# Sheet1.net
KiCad netlist of a schematic drawn in Altium Designer
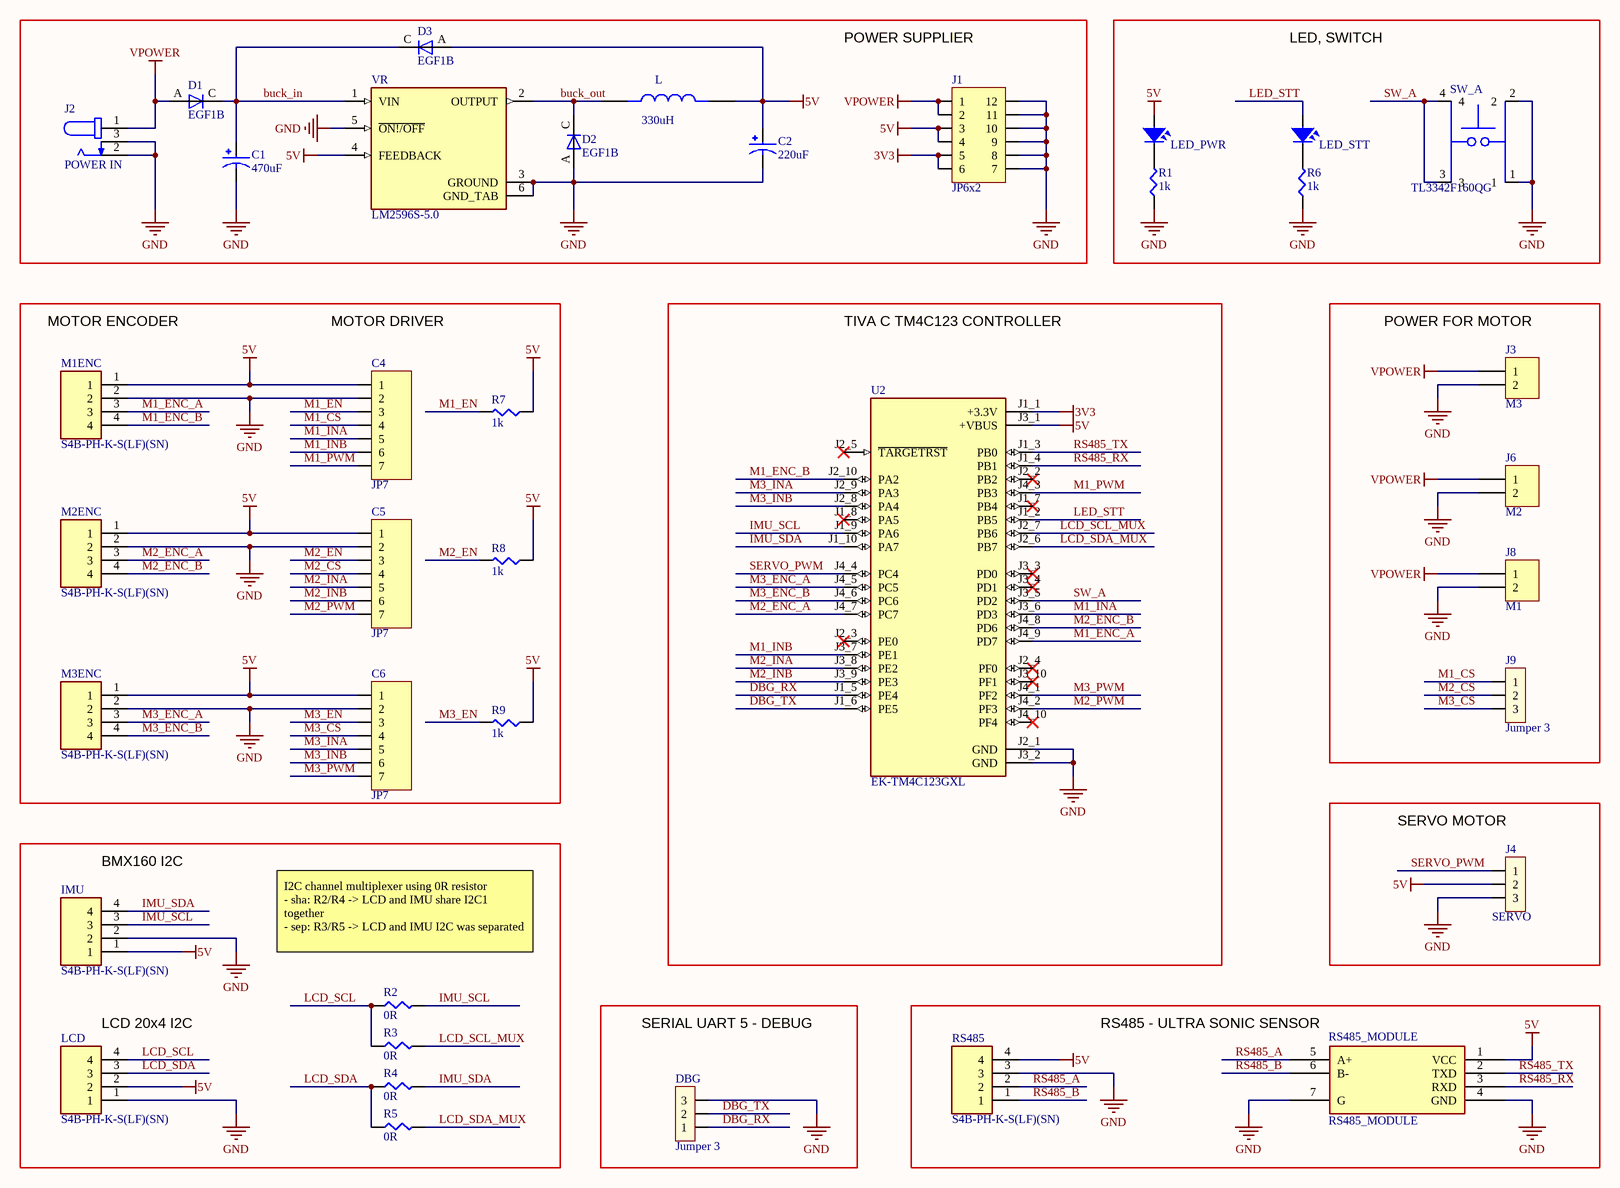
[diagram p0: Sheet1.SchDoc]

(export (version "E")
  (design (tool "Eeschema 10.0.6"))
  (components
    (comp (ref "C1")
      (value "470uF")
      (footprint "CAP_EEE2AA220P")
      (description "Capacitor; Alum Electrolytic; Cap 22 uF; Tol 20%; Vol-Rtg 100 VDC; SMT; 10x10.5; TR")
      (fields (field (name "MF") "Panasonic") (field (name "MP") "EEE-2AA220P"))
      (libsource (lib "EEE2AA220P") (part "EEE2AA220P"))
    )
    (comp (ref "C2")
      (value "220uF")
      (footprint "CAP_EEEHB1V220P")
      (description "EEE-HB Series 35 V 22 uF Ã˜ 6.3 x 5.8 mm 105 Â°C SMT V-Chip Aluminum Electrolytic")
      (fields (field (name "MP") "EEEHB1V220P") (field (name "MF") "Panasonic"))
      (libsource (lib "EEEHB1V220P") (part "EEEHB1V220P"))
    )
    (comp (ref "C4")
      (value "JP7")
      (footprint "JP7-C1T")
      (description "WR-PHD 2.54 mm Angled Socket Header")
      (fields
        (field (name "MANUFACTURER") "Würth Elektronik eiSos GmbH")
        (field (name "PARTNO") "613007143121")
        (field (name "CREATED BY") "Karrer Zheng")
      )
      (libsource (lib "My Library") (part "JP7_1"))
    )
    (comp (ref "C5")
      (value "JP7")
      (footprint "JP7-C1T")
      (description "WR-PHD 2.54 mm Angled Socket Header")
      (fields
        (field (name "MANUFACTURER") "Würth Elektronik eiSos GmbH")
        (field (name "PARTNO") "613007143121")
        (field (name "CREATED BY") "Karrer Zheng")
      )
      (libsource (lib "My Library") (part "JP7_1"))
    )
    (comp (ref "C6")
      (value "JP7")
      (footprint "JP7-C1T")
      (description "WR-PHD 2.54 mm Angled Socket Header")
      (fields
        (field (name "MANUFACTURER") "Würth Elektronik eiSos GmbH")
        (field (name "PARTNO") "613007143121")
        (field (name "CREATED BY") "Karrer Zheng")
      )
      (libsource (lib "My Library") (part "JP7_1"))
    )
    (comp (ref "D1")
      (value "EGF1B")
      (footprint "DIOM449X264X300L114X135N")
      (description "SS54 SMA\r\nDiode Shotky SS54 1N5824 5A 40V")
      (fields (field (name "MF") "ON Semiconductor"))
      (libsource (lib "EGF1B") (part "EGF1B"))
    )
    (comp (ref "D2")
      (value "EGF1B")
      (footprint "DIOM449X264X300L114X135N")
      (description "SS54 SMA\r\nDiode Shotky SS54 1N5824 5A 40V")
      (fields (field (name "MF") "ON Semiconductor"))
      (libsource (lib "EGF1B") (part "EGF1B"))
    )
    (comp (ref "D3")
      (value "EGF1B")
      (footprint "DIOM449X264X300L114X135N")
      (description "SS54 SMA\r\nDiode Shotky SS54 1N5824 5A 40V")
      (fields (field (name "MF") "ON Semiconductor"))
      (libsource (lib "EGF1B") (part "EGF1B"))
    )
    (comp (ref "DBG") (value "Jumper 3") (footprint "JP3") (libsource (lib "") (part "JP3_1")))
    (comp (ref "IMU")
      (value "S4B-PH-K-S(LF)(SN)")
      (footprint "JST_S4B-PH-K-S(LF)(SN)")
      (description "Connector Header Through Hole, Right Angle 4 position 0.079 _2.00mm_")
      (fields (field (name "MP") "S4B-PH-K-S_LF__SN_") (field (name "MF") "JST Sales"))
      (libsource (lib "") (part "S4B-PH-K-S(LF)(SN)_1"))
    )
    (comp (ref "J1")
      (value "JP6x2")
      (footprint "JP6-D2T")
      (description "WR-PHD 2.54 mm Dual Socket Header")
      (fields
        (field (name "MANUFACTURER") "Würth Elektronik eiSos GmbH")
        (field (name "PARTNO") "61301221821")
        (field (name "CREATED BY") "Karrer Zheng")
      )
      (libsource (lib "My Library") (part "JP6x2"))
    )
    (comp (ref "J2")
      (value "POWER IN")
      (footprint "CUI_PJ-002B")
      (description "2.5 x 6.5 mm, 2.5 A, Horizontal, Through Hole, Dc Power Jack Connector")
      (fields (field (name "MF") "CUI Devices") (field (name "MP") "PJ-002B"))
      (libsource (lib "PJ-002B") (part "PJ-002B"))
    )
    (comp (ref "J3")
      (value "M3")
      (footprint "KF2-3.5")
      (fields
        (field (name "MANUFACTURER") "Würth Elektronik eiSos GmbH")
        (field (name "PARTNO") "691103110002")
        (field (name "CREATED BY") "Karrer Zheng")
      )
      (libsource (lib "My Library") (part "KF2"))
    )
    (comp (ref "J4") (value "SERVO") (footprint "JP3") (libsource (lib "My Library") (part "JP3")))
    (comp (ref "J6")
      (value "M2")
      (footprint "KF2-3.5")
      (fields
        (field (name "MANUFACTURER") "Würth Elektronik eiSos GmbH")
        (field (name "PARTNO") "691103110002")
        (field (name "CREATED BY") "Karrer Zheng")
      )
      (libsource (lib "My Library") (part "KF2"))
    )
    (comp (ref "J8")
      (value "M1")
      (footprint "KF2-3.5")
      (fields
        (field (name "MANUFACTURER") "Würth Elektronik eiSos GmbH")
        (field (name "PARTNO") "691103110002")
        (field (name "CREATED BY") "Karrer Zheng")
      )
      (libsource (lib "My Library") (part "KF2"))
    )
    (comp (ref "J9") (value "Jumper 3") (footprint "JP3") (libsource (lib "My Library") (part "JP3")))
    (comp (ref "L")
      (value "330uH")
      (footprint "IND_B1047AS-331M=P3")
      (description "Inductor with Inductance: 330uH Tol. +/-20%, Package: 2929 (7373)")
      (fields (field (name "MF") "Murata") (field (name "MP") "B1047AS-331M=P3"))
      (libsource (lib "B1047AS-331M_P3") (part "B1047AS-331M=P3"))
    )
    (comp (ref "LCD")
      (value "S4B-PH-K-S(LF)(SN)")
      (footprint "JST_S4B-PH-K-S(LF)(SN)")
      (description "Connector Header Through Hole, Right Angle 4 position 0.079 _2.00mm_")
      (fields (field (name "MP") "S4B-PH-K-S_LF__SN_") (field (name "MF") "JST Sales"))
      (libsource (lib "") (part "S4B-PH-K-S(LF)(SN)_1"))
    )
    (comp (ref "LED_PWR")
      (value "PWR LED")
      (footprint "LED-0805-Green")
      (libsource (lib "My Library") (part "LED SMD"))
    )
    (comp (ref "LED_STT")
      (value "LED")
      (footprint "LED-0805-Green")
      (libsource (lib "My Library") (part "LED SMD"))
    )
    (comp (ref "M1ENC")
      (value "S4B-PH-K-S(LF)(SN)")
      (footprint "JST_S4B-PH-K-S(LF)(SN)")
      (description "Connector Header Through Hole, Right Angle 4 position 0.079 _2.00mm_")
      (fields (field (name "MP") "S4B-PH-K-S_LF__SN_") (field (name "MF") "JST Sales"))
      (libsource (lib "S4B-PH-K-S_LF__SN_") (part "S4B-PH-K-S(LF)(SN)"))
    )
    (comp (ref "M2ENC")
      (value "S4B-PH-K-S(LF)(SN)")
      (footprint "JST_S4B-PH-K-S(LF)(SN)")
      (description "Connector Header Through Hole, Right Angle 4 position 0.079 _2.00mm_")
      (fields (field (name "MP") "S4B-PH-K-S_LF__SN_") (field (name "MF") "JST Sales"))
      (libsource (lib "S4B-PH-K-S_LF__SN_") (part "S4B-PH-K-S(LF)(SN)"))
    )
    (comp (ref "M3ENC")
      (value "S4B-PH-K-S(LF)(SN)")
      (footprint "JST_S4B-PH-K-S(LF)(SN)")
      (description "Connector Header Through Hole, Right Angle 4 position 0.079 _2.00mm_")
      (fields (field (name "MP") "S4B-PH-K-S_LF__SN_") (field (name "MF") "JST Sales"))
      (libsource (lib "S4B-PH-K-S_LF__SN_") (part "S4B-PH-K-S(LF)(SN)"))
    )
    (comp (ref "R1")
      (value "1k")
      (footprint "SMD-0805-RES")
      (description "RES SMD 0805")
      (fields (field (name "PART NUMBER") "ERJ-S6SJR20V") (field (name "DIGI-KEY PART NUMBER") "P.2BKCT-ND"))
      (libsource (lib "Panasonic_ERJ_0805") (part "Res SMD 0805"))
    )
    (comp (ref "R2")
      (value "0R")
      (footprint "SMD-0805-RES")
      (description "RES SMD 0805")
      (fields (field (name "PART NUMBER") "ERJ-S6SJR20V") (field (name "DIGI-KEY PART NUMBER") "P.2BKCT-ND"))
      (libsource (lib "Panasonic_ERJ_0805") (part "Res SMD 0805"))
    )
    (comp (ref "R3")
      (value "0R")
      (footprint "SMD-0805-RES")
      (description "RES SMD 0805")
      (fields (field (name "PART NUMBER") "ERJ-S6SJR20V") (field (name "DIGI-KEY PART NUMBER") "P.2BKCT-ND"))
      (libsource (lib "Panasonic_ERJ_0805") (part "Res SMD 0805"))
    )
    (comp (ref "R4")
      (value "0R")
      (footprint "SMD-0805-RES")
      (description "RES SMD 0805")
      (fields (field (name "PART NUMBER") "ERJ-S6SJR20V") (field (name "DIGI-KEY PART NUMBER") "P.2BKCT-ND"))
      (libsource (lib "Panasonic_ERJ_0805") (part "Res SMD 0805"))
    )
    (comp (ref "R5")
      (value "0R")
      (footprint "SMD-0805-RES")
      (description "RES SMD 0805")
      (fields (field (name "PART NUMBER") "ERJ-S6SJR20V") (field (name "DIGI-KEY PART NUMBER") "P.2BKCT-ND"))
      (libsource (lib "Panasonic_ERJ_0805") (part "Res SMD 0805"))
    )
    (comp (ref "R6")
      (value "1k")
      (footprint "SMD-0805-RES")
      (description "RES SMD 0805")
      (fields (field (name "PART NUMBER") "ERJ-S6SJR20V") (field (name "DIGI-KEY PART NUMBER") "P.2BKCT-ND"))
      (libsource (lib "Panasonic_ERJ_0805") (part "Res SMD 0805"))
    )
    (comp (ref "R7")
      (value "1k")
      (footprint "SMD-0805-RES")
      (description "RES SMD 0805")
      (fields (field (name "PART NUMBER") "ERJ-S6SJR20V") (field (name "DIGI-KEY PART NUMBER") "P.2BKCT-ND"))
      (libsource (lib "Panasonic_ERJ_0805") (part "Res SMD 0805"))
    )
    (comp (ref "R8")
      (value "1k")
      (footprint "SMD-0805-RES")
      (description "RES SMD 0805")
      (fields (field (name "PART NUMBER") "ERJ-S6SJR20V") (field (name "DIGI-KEY PART NUMBER") "P.2BKCT-ND"))
      (libsource (lib "Panasonic_ERJ_0805") (part "Res SMD 0805"))
    )
    (comp (ref "R9")
      (value "1k")
      (footprint "SMD-0805-RES")
      (description "RES SMD 0805")
      (fields (field (name "PART NUMBER") "ERJ-S6SJR20V") (field (name "DIGI-KEY PART NUMBER") "P.2BKCT-ND"))
      (libsource (lib "Panasonic_ERJ_0805") (part "Res SMD 0805"))
    )
    (comp (ref "RS485")
      (value "S4B-PH-K-S(LF)(SN)")
      (footprint "JST_S4B-PH-K-S(LF)(SN)")
      (description "Connector Header Through Hole, Right Angle 4 position 0.079 _2.00mm_")
      (fields (field (name "MP") "S4B-PH-K-S_LF__SN_") (field (name "MF") "JST Sales"))
      (libsource (lib "") (part "S4B-PH-K-S(LF)(SN)_1"))
    )
    (comp (ref "RS485_MODULE")
      (value "RS485_MODULE")
      (footprint "RS485_MODULE")
      (libsource (lib "custom_lib") (part "RS485_MODULE"))
    )
    (comp (ref "SW_A")
      (value "TL3342F160QG")
      (footprint "SW_TL3342F160QG")
      (description "Tactile Switch SPST-NO Top Actuated Surface Mount")
      (fields (field (name "MF") "E-Switch"))
      (libsource (lib "TL3342F160QG") (part "TL3342F160QG"))
    )
    (comp (ref "U2")
      (value "EK-TM4C123GXL")
      (footprint "MODULE_EK-TM4C123GXL")
      (description "ARMÂ® CortexÂ®-M4F Based MCU TM4C123G LaunchPadâ„¢ Evaluation Kit")
      (fields (field (name "MF") "Texas Instruments"))
      (libsource (lib "EK-TM4C123GXL") (part "EK-TM4C123GXL"))
    )
    (comp (ref "VR")
      (value "LM2596S-5.0")
      (footprint "TO170P1524X483-6N")
      (description "SIMPLE SWITCHER&reg; 4.5V to 40V, 3A Low Component Count Step-Down Regulator 5-DDPAK/TO-263")
      (fields (field (name "MF") "Texas Instruments") (field (name "MP") "LM2596S-5.0/NOPB"))
      (libsource (lib "LM2596S-5.0") (part "LM2596S-5.0"))
    )
  )
  (nets
    (net (code "1") (name "/DBG_RX") (class "Default")
      (node (ref "DBG") (pin "1") (pinfunction "1_1") (pintype "passive"))
      (node (ref "U2") (pin "J1_5") (pinfunction "PE4_J1_5") (pintype "bidirectional"))
    )
    (net (code "2") (name "/DBG_TX") (class "Default")
      (node (ref "DBG") (pin "2") (pinfunction "2_2") (pintype "passive"))
      (node (ref "U2") (pin "J1_6") (pinfunction "PE5_J1_6") (pintype "bidirectional"))
    )
    (net (code "3") (name "/IMU_SCL") (class "Default")
      (node (ref "IMU") (pin "3") (pinfunction "3_3") (pintype "passive"))
      (node (ref "R2") (pin "2") (pinfunction "2_2") (pintype "passive"))
      (node (ref "U2") (pin "J1_9") (pinfunction "PA6_J1_9") (pintype "bidirectional"))
    )
    (net (code "4") (name "/IMU_SDA") (class "Default")
      (node (ref "IMU") (pin "4") (pinfunction "4_4") (pintype "passive"))
      (node (ref "R4") (pin "2") (pinfunction "2_2") (pintype "passive"))
      (node (ref "U2") (pin "J1_10") (pinfunction "PA7_J1_10") (pintype "bidirectional"))
    )
    (net (code "5") (name "/LCD_SCL") (class "Default")
      (node (ref "LCD") (pin "4") (pinfunction "4_4") (pintype "passive"))
      (node (ref "R2") (pin "1") (pinfunction "1_1") (pintype "passive"))
      (node (ref "R3") (pin "1") (pinfunction "1_1") (pintype "passive"))
    )
    (net (code "6") (name "/LCD_SCL_MUX") (class "Default")
      (node (ref "R3") (pin "2") (pinfunction "2_2") (pintype "passive"))
      (node (ref "U2") (pin "J2_7") (pinfunction "PB6_J2_7") (pintype "bidirectional"))
    )
    (net (code "7") (name "/LCD_SDA") (class "Default")
      (node (ref "LCD") (pin "3") (pinfunction "3_3") (pintype "passive"))
      (node (ref "R4") (pin "1") (pinfunction "1_1") (pintype "passive"))
      (node (ref "R5") (pin "1") (pinfunction "1_1") (pintype "passive"))
    )
    (net (code "8") (name "/LCD_SDA_MUX") (class "Default")
      (node (ref "R5") (pin "2") (pinfunction "2_2") (pintype "passive"))
      (node (ref "U2") (pin "J2_6") (pinfunction "PB7_J2_6") (pintype "bidirectional"))
    )
    (net (code "9") (name "/LED_STT") (class "Default")
      (node (ref "LED_STT") (pin "1") (pinfunction "1_1") (pintype "passive"))
      (node (ref "U2") (pin "J1_2") (pinfunction "PB5_J1_2") (pintype "bidirectional"))
    )
    (net (code "10") (name "/M1_CS") (class "Default")
      (node (ref "C4") (pin "4") (pinfunction "4_4") (pintype "passive"))
      (node (ref "J9") (pin "1") (pinfunction "1_1") (pintype "passive"))
    )
    (net (code "11") (name "/M1_EN") (class "Default")
      (node (ref "C4") (pin "3") (pinfunction "3_3") (pintype "passive"))
      (node (ref "R7") (pin "2") (pinfunction "2_2") (pintype "passive"))
    )
    (net (code "12") (name "/M1_ENC_A") (class "Default")
      (node (ref "M1ENC") (pin "3") (pinfunction "3_3") (pintype "passive"))
      (node (ref "U2") (pin "J4_9") (pinfunction "PD7_J4_9") (pintype "bidirectional"))
    )
    (net (code "13") (name "/M1_ENC_B") (class "Default")
      (node (ref "M1ENC") (pin "4") (pinfunction "4_4") (pintype "passive"))
      (node (ref "U2") (pin "J2_10") (pinfunction "PA2_J2_10") (pintype "bidirectional"))
    )
    (net (code "14") (name "/M1_INA") (class "Default")
      (node (ref "C4") (pin "5") (pinfunction "5_5") (pintype "passive"))
      (node (ref "U2") (pin "J3_6") (pinfunction "PD3_J3_6") (pintype "bidirectional"))
    )
    (net (code "15") (name "/M1_INB") (class "Default")
      (node (ref "C4") (pin "6") (pinfunction "6_6") (pintype "passive"))
      (node (ref "U2") (pin "J3_7") (pinfunction "PE1_J3_7") (pintype "bidirectional"))
    )
    (net (code "16") (name "/M1_PWM") (class "Default")
      (node (ref "C4") (pin "7") (pinfunction "7_7") (pintype "passive"))
      (node (ref "U2") (pin "J4_3") (pinfunction "PB3_J4_3") (pintype "bidirectional"))
    )
    (net (code "17") (name "/M2_CS") (class "Default")
      (node (ref "C5") (pin "4") (pinfunction "4_4") (pintype "passive"))
      (node (ref "J9") (pin "2") (pinfunction "2_2") (pintype "passive"))
    )
    (net (code "18") (name "/M2_EN") (class "Default")
      (node (ref "C5") (pin "3") (pinfunction "3_3") (pintype "passive"))
      (node (ref "R8") (pin "2") (pinfunction "2_2") (pintype "passive"))
    )
    (net (code "19") (name "/M2_ENC_A") (class "Default")
      (node (ref "M2ENC") (pin "3") (pinfunction "3_3") (pintype "passive"))
      (node (ref "U2") (pin "J4_7") (pinfunction "PC7_J4_7") (pintype "bidirectional"))
    )
    (net (code "20") (name "/M2_ENC_B") (class "Default")
      (node (ref "M2ENC") (pin "4") (pinfunction "4_4") (pintype "passive"))
      (node (ref "U2") (pin "J4_8") (pinfunction "PD6_J4_8") (pintype "bidirectional"))
    )
    (net (code "21") (name "/M2_INA") (class "Default")
      (node (ref "C5") (pin "5") (pinfunction "5_5") (pintype "passive"))
      (node (ref "U2") (pin "J3_8") (pinfunction "PE2_J3_8") (pintype "bidirectional"))
    )
    (net (code "22") (name "/M2_INB") (class "Default")
      (node (ref "C5") (pin "6") (pinfunction "6_6") (pintype "passive"))
      (node (ref "U2") (pin "J3_9") (pinfunction "PE3_J3_9") (pintype "bidirectional"))
    )
    (net (code "23") (name "/M2_PWM") (class "Default")
      (node (ref "C5") (pin "7") (pinfunction "7_7") (pintype "passive"))
      (node (ref "U2") (pin "J4_2") (pinfunction "PF3_J4_2") (pintype "bidirectional"))
    )
    (net (code "24") (name "/M3_CS") (class "Default")
      (node (ref "C6") (pin "4") (pinfunction "4_4") (pintype "passive"))
      (node (ref "J9") (pin "3") (pinfunction "3_3") (pintype "passive"))
    )
    (net (code "25") (name "/M3_EN") (class "Default")
      (node (ref "C6") (pin "3") (pinfunction "3_3") (pintype "passive"))
      (node (ref "R9") (pin "2") (pinfunction "2_2") (pintype "passive"))
    )
    (net (code "26") (name "/M3_ENC_A") (class "Default")
      (node (ref "M3ENC") (pin "3") (pinfunction "3_3") (pintype "passive"))
      (node (ref "U2") (pin "J4_5") (pinfunction "PC5_J4_5") (pintype "bidirectional"))
    )
    (net (code "27") (name "/M3_ENC_B") (class "Default")
      (node (ref "M3ENC") (pin "4") (pinfunction "4_4") (pintype "passive"))
      (node (ref "U2") (pin "J4_6") (pinfunction "PC6_J4_6") (pintype "bidirectional"))
    )
    (net (code "28") (name "/M3_INA") (class "Default")
      (node (ref "C6") (pin "5") (pinfunction "5_5") (pintype "passive"))
      (node (ref "U2") (pin "J2_9") (pinfunction "PA3_J2_9") (pintype "bidirectional"))
    )
    (net (code "29") (name "/M3_INB") (class "Default")
      (node (ref "C6") (pin "6") (pinfunction "6_6") (pintype "passive"))
      (node (ref "U2") (pin "J2_8") (pinfunction "PA4_J2_8") (pintype "bidirectional"))
    )
    (net (code "30") (name "/M3_PWM") (class "Default")
      (node (ref "C6") (pin "7") (pinfunction "7_7") (pintype "passive"))
      (node (ref "U2") (pin "J4_1") (pinfunction "PF2_J4_1") (pintype "bidirectional"))
    )
    (net (code "31") (name "/RS485_A") (class "Default")
      (node (ref "RS485") (pin "2") (pinfunction "2_2") (pintype "passive"))
      (node (ref "RS485_MODULE") (pin "5") (pinfunction "A+_5") (pintype "passive"))
    )
    (net (code "32") (name "/RS485_B") (class "Default")
      (node (ref "RS485") (pin "1") (pinfunction "1_1") (pintype "passive"))
      (node (ref "RS485_MODULE") (pin "6") (pinfunction "B-_6") (pintype "passive"))
    )
    (net (code "33") (name "/RS485_RX") (class "Default")
      (node (ref "RS485_MODULE") (pin "3") (pinfunction "RXD_3") (pintype "passive"))
      (node (ref "U2") (pin "J1_4") (pinfunction "PB1_J1_4") (pintype "bidirectional"))
    )
    (net (code "34") (name "/RS485_TX") (class "Default")
      (node (ref "RS485_MODULE") (pin "2") (pinfunction "TXD_2") (pintype "passive"))
      (node (ref "U2") (pin "J1_3") (pinfunction "PB0_J1_3") (pintype "bidirectional"))
    )
    (net (code "35") (name "/SERVO_PWM") (class "Default")
      (node (ref "J4") (pin "1") (pinfunction "1_1") (pintype "passive"))
      (node (ref "U2") (pin "J4_4") (pinfunction "PC4_J4_4") (pintype "bidirectional"))
    )
    (net (code "36") (name "/SW_A") (class "Default")
      (node (ref "SW_A") (pin "3") (pinfunction "3_3") (pintype "passive"))
      (node (ref "SW_A") (pin "4") (pinfunction "4_4") (pintype "passive"))
      (node (ref "U2") (pin "J3_5") (pinfunction "PD2_J3_5") (pintype "bidirectional"))
    )
    (net (code "37") (name "/buck_in") (class "Default")
      (node (ref "C1") (pin "1") (pinfunction "1_1") (pintype "passive"))
      (node (ref "D1") (pin "C") (pinfunction "C_C") (pintype "passive"))
      (node (ref "D3") (pin "C") (pinfunction "C_C") (pintype "passive"))
      (node (ref "VR") (pin "1") (pinfunction "VIN_1") (pintype "input"))
    )
    (net (code "38") (name "/buck_out") (class "Default")
      (node (ref "D2") (pin "C") (pinfunction "C_C") (pintype "passive"))
      (node (ref "L") (pin "1") (pinfunction "1_1") (pintype "passive"))
      (node (ref "VR") (pin "2") (pinfunction "OUTPUT_2") (pintype "output"))
    )
    (net (code "39") (name "3V3") (class "Default")
      (node (ref "J1") (pin "5") (pinfunction "5_5") (pintype "passive"))
      (node (ref "J1") (pin "6") (pinfunction "6_6") (pintype "passive"))
      (node (ref "U2") (pin "J1_1") (pinfunction "+3.3V_J1_1") (pintype "power_in"))
    )
    (net (code "40") (name "5V") (class "Default")
      (node (ref "C2") (pin "1") (pinfunction "1_1") (pintype "passive"))
      (node (ref "C4") (pin "1") (pinfunction "1_1") (pintype "passive"))
      (node (ref "C5") (pin "1") (pinfunction "1_1") (pintype "passive"))
      (node (ref "C6") (pin "1") (pinfunction "1_1") (pintype "passive"))
      (node (ref "D3") (pin "A") (pinfunction "A_A") (pintype "passive"))
      (node (ref "IMU") (pin "1") (pinfunction "1_1") (pintype "passive"))
      (node (ref "J1") (pin "3") (pinfunction "3_3") (pintype "passive"))
      (node (ref "J1") (pin "4") (pinfunction "4_4") (pintype "passive"))
      (node (ref "J4") (pin "2") (pinfunction "2_2") (pintype "passive"))
      (node (ref "L") (pin "2") (pinfunction "2_2") (pintype "passive"))
      (node (ref "LCD") (pin "2") (pinfunction "2_2") (pintype "passive"))
      (node (ref "LED_PWR") (pin "1") (pinfunction "1_1") (pintype "passive"))
      (node (ref "M1ENC") (pin "1") (pinfunction "1_1") (pintype "passive"))
      (node (ref "M2ENC") (pin "1") (pinfunction "1_1") (pintype "passive"))
      (node (ref "M3ENC") (pin "1") (pinfunction "1_1") (pintype "passive"))
      (node (ref "R7") (pin "1") (pinfunction "1_1") (pintype "passive"))
      (node (ref "R8") (pin "1") (pinfunction "1_1") (pintype "passive"))
      (node (ref "R9") (pin "1") (pinfunction "1_1") (pintype "passive"))
      (node (ref "RS485") (pin "4") (pinfunction "4_4") (pintype "passive"))
      (node (ref "RS485_MODULE") (pin "1") (pinfunction "VCC_1") (pintype "passive"))
      (node (ref "U2") (pin "J3_1") (pinfunction "+VBUS_J3_1") (pintype "power_in"))
      (node (ref "VR") (pin "4") (pinfunction "FEEDBACK_4") (pintype "input"))
    )
    (net (code "41") (name "GND") (class "Default")
      (node (ref "C1") (pin "2") (pinfunction "2_2") (pintype "passive"))
      (node (ref "C2") (pin "2") (pinfunction "2_2") (pintype "passive"))
      (node (ref "C4") (pin "2") (pinfunction "2_2") (pintype "passive"))
      (node (ref "C5") (pin "2") (pinfunction "2_2") (pintype "passive"))
      (node (ref "C6") (pin "2") (pinfunction "2_2") (pintype "passive"))
      (node (ref "D2") (pin "A") (pinfunction "A_A") (pintype "passive"))
      (node (ref "DBG") (pin "3") (pinfunction "3_3") (pintype "passive"))
      (node (ref "IMU") (pin "2") (pinfunction "2_2") (pintype "passive"))
      (node (ref "J1") (pin "10") (pinfunction "10_10") (pintype "passive"))
      (node (ref "J1") (pin "11") (pinfunction "11_11") (pintype "passive"))
      (node (ref "J1") (pin "12") (pinfunction "12_12") (pintype "passive"))
      (node (ref "J1") (pin "7") (pinfunction "7_7") (pintype "passive"))
      (node (ref "J1") (pin "8") (pinfunction "8_8") (pintype "passive"))
      (node (ref "J1") (pin "9") (pinfunction "9_9") (pintype "passive"))
      (node (ref "J2") (pin "2") (pinfunction "2_2") (pintype "passive"))
      (node (ref "J2") (pin "3") (pinfunction "3_3") (pintype "passive"))
      (node (ref "J3") (pin "2") (pinfunction "2_2") (pintype "passive"))
      (node (ref "J4") (pin "3") (pinfunction "3_3") (pintype "passive"))
      (node (ref "J6") (pin "2") (pinfunction "2_2") (pintype "passive"))
      (node (ref "J8") (pin "2") (pinfunction "2_2") (pintype "passive"))
      (node (ref "LCD") (pin "1") (pinfunction "1_1") (pintype "passive"))
      (node (ref "M1ENC") (pin "2") (pinfunction "2_2") (pintype "passive"))
      (node (ref "M2ENC") (pin "2") (pinfunction "2_2") (pintype "passive"))
      (node (ref "M3ENC") (pin "2") (pinfunction "2_2") (pintype "passive"))
      (node (ref "R1") (pin "1") (pinfunction "1_1") (pintype "passive"))
      (node (ref "R6") (pin "1") (pinfunction "1_1") (pintype "passive"))
      (node (ref "RS485") (pin "3") (pinfunction "3_3") (pintype "passive"))
      (node (ref "RS485_MODULE") (pin "4") (pinfunction "GND_4") (pintype "passive"))
      (node (ref "RS485_MODULE") (pin "7") (pinfunction "G_7") (pintype "passive"))
      (node (ref "SW_A") (pin "1") (pinfunction "1_1") (pintype "passive"))
      (node (ref "SW_A") (pin "2") (pinfunction "2_2") (pintype "passive"))
      (node (ref "U2") (pin "J2_1") (pinfunction "GND_J2_1") (pintype "power_in"))
      (node (ref "U2") (pin "J3_2") (pinfunction "GND_J3_2") (pintype "power_in"))
      (node (ref "VR") (pin "3") (pinfunction "GROUND_3") (pintype "power_in"))
      (node (ref "VR") (pin "5") (pinfunction "~{ON!/OFF}_5") (pintype "input"))
      (node (ref "VR") (pin "6") (pinfunction "GND_TAB_6") (pintype "power_in"))
    )
    (net (code "42") (name "Net-(LED_PWR-Pad2)") (class "Default")
      (node (ref "LED_PWR") (pin "2") (pinfunction "2_2") (pintype "passive"))
      (node (ref "R1") (pin "2") (pinfunction "2_2") (pintype "passive"))
    )
    (net (code "43") (name "Net-(LED_STT-Pad2)") (class "Default")
      (node (ref "LED_STT") (pin "2") (pinfunction "2_2") (pintype "passive"))
      (node (ref "R6") (pin "2") (pinfunction "2_2") (pintype "passive"))
    )
    (net (code "44") (name "VPOWER") (class "Default")
      (node (ref "D1") (pin "A") (pinfunction "A_A") (pintype "passive"))
      (node (ref "J1") (pin "1") (pinfunction "1_1") (pintype "passive"))
      (node (ref "J1") (pin "2") (pinfunction "2_2") (pintype "passive"))
      (node (ref "J2") (pin "1") (pinfunction "1_1") (pintype "passive"))
      (node (ref "J3") (pin "1") (pinfunction "1_1") (pintype "passive"))
      (node (ref "J6") (pin "1") (pinfunction "1_1") (pintype "passive"))
      (node (ref "J8") (pin "1") (pinfunction "1_1") (pintype "passive"))
    )
    (net (code "45") (name "unconnected-(U2-PA5-PadJ1_8)") (class "Default")
      (node (ref "U2") (pin "J1_8") (pinfunction "PA5_J1_8") (pintype "bidirectional+no_connect"))
    )
    (net (code "46") (name "unconnected-(U2-PB2-PadJ2_2)") (class "Default")
      (node (ref "U2") (pin "J2_2") (pinfunction "PB2_J2_2") (pintype "bidirectional+no_connect"))
    )
    (net (code "47") (name "unconnected-(U2-PB4-PadJ1_7)") (class "Default")
      (node (ref "U2") (pin "J1_7") (pinfunction "PB4_J1_7") (pintype "bidirectional+no_connect"))
    )
    (net (code "48") (name "unconnected-(U2-PD0-PadJ3_3)") (class "Default")
      (node (ref "U2") (pin "J3_3") (pinfunction "PD0_J3_3") (pintype "bidirectional+no_connect"))
    )
    (net (code "49") (name "unconnected-(U2-PD1-PadJ3_4)") (class "Default")
      (node (ref "U2") (pin "J3_4") (pinfunction "PD1_J3_4") (pintype "bidirectional+no_connect"))
    )
    (net (code "50") (name "unconnected-(U2-PE0-PadJ2_3)") (class "Default")
      (node (ref "U2") (pin "J2_3") (pinfunction "PE0_J2_3") (pintype "bidirectional+no_connect"))
    )
    (net (code "51") (name "unconnected-(U2-PF0-PadJ2_4)") (class "Default")
      (node (ref "U2") (pin "J2_4") (pinfunction "PF0_J2_4") (pintype "bidirectional+no_connect"))
    )
    (net (code "52") (name "unconnected-(U2-PF1-PadJ3_10)") (class "Default")
      (node (ref "U2") (pin "J3_10") (pinfunction "PF1_J3_10") (pintype "bidirectional+no_connect"))
    )
    (net (code "53") (name "unconnected-(U2-PF4-PadJ4_10)") (class "Default")
      (node (ref "U2") (pin "J4_10") (pinfunction "PF4_J4_10") (pintype "bidirectional+no_connect"))
    )
    (net (code "54") (name "unconnected-(U2-~{TARGETRST}-PadJ2_5)") (class "Default")
      (node (ref "U2") (pin "J2_5") (pinfunction "~{TARGETRST}_J2_5") (pintype "input+no_connect"))
    )
  )
)
